# Power.net
KiCad netlist of a schematic drawn in Altium Designer
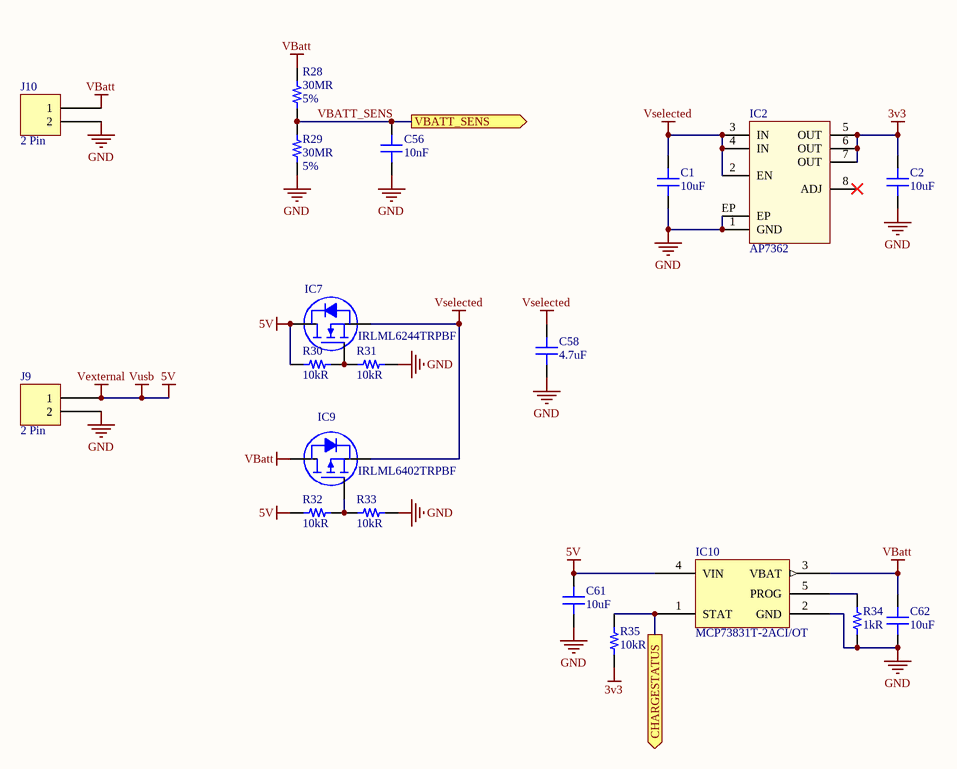
[diagram p0: Power.SchDoc]

(export (version "E")
  (design (tool "Eeschema 10.0.6"))
  (components
    (comp (ref "C1")
      (value "10uF")
      (footprint "CAP 0603/1608")
      (description "Ceramic, SMT Capacitor")
      (fields
        (field (name "MANUFACTURER") "Samsung")
        (field (name "MANUFACTURER PART NUMBER") "CL10A106MQ8NNNC")
      )
      (libsource (lib "yildizIoT Library") (part "Capacitor - Ceramic"))
    )
    (comp (ref "C2")
      (value "10uF")
      (footprint "CAP 0603/1608")
      (description "Ceramic, SMT Capacitor")
      (fields
        (field (name "MANUFACTURER") "Samsung")
        (field (name "MANUFACTURER PART NUMBER") "CL10A106MQ8NNNC")
      )
      (libsource (lib "yildizIoT Library") (part "Capacitor - Ceramic"))
    )
    (comp (ref "C56")
      (value "10nF")
      (footprint "CAP 0603/1608")
      (description "Ceramic, SMT Capacitor")
      (fields
        (field (name "MANUFACTURER") "KEMET")
        (field (name "MANUFACTURER PART NUMBER") "C0603C103J5RACTU")
      )
      (libsource (lib "yildizIoT Library") (part "Capacitor - Ceramic"))
    )
    (comp (ref "C58")
      (value "4.7uF")
      (footprint "CAP 0603/1608")
      (description "Ceramic, SMT Capacitor")
      (fields
        (field (name "MANUFACTURER") "Samsung")
        (field (name "MANUFACTURER PART NUMBER") "CL10A475MQ8NNNC")
      )
      (libsource (lib "yildizIoT Library") (part "Capacitor - Ceramic"))
    )
    (comp (ref "C61")
      (value "10uF")
      (footprint "CAP 0603/1608")
      (description "Ceramic, SMT Capacitor")
      (fields
        (field (name "MANUFACTURER") "Samsung")
        (field (name "MANUFACTURER PART NUMBER") "CL10A106MQ8NNNC")
      )
      (libsource (lib "yildizIoT Library") (part "Capacitor - Ceramic"))
    )
    (comp (ref "C62")
      (value "10uF")
      (footprint "CAP 0603/1608")
      (description "Ceramic, SMT Capacitor")
      (fields
        (field (name "MANUFACTURER") "Samsung")
        (field (name "MANUFACTURER PART NUMBER") "CL10A106MQ8NNNC")
      )
      (libsource (lib "yildizIoT Library") (part "Capacitor - Ceramic"))
    )
    (comp (ref "IC2")
      (value "AP7362")
      (footprint "DIODES SO-8-EP")
      (description "The AP7362 is a 1.5A adjustable output voltage linear regulator with ultra-low dropout.")
      (fields
        (field (name "MANUFACTURER") "Diodes")
        (field (name "MANUFACTURER PART NUMBER") "AP7362-33SP-13")
      )
      (libsource (lib "yildizIoT Library") (part "DIODES AP7362"))
    )
    (comp (ref "IC7")
      (value "IRLML6244TRPBF")
      (footprint "INFINEON SOT-23-3")
      (description "MOSFET N-CH 20V 6.3A SOT-23")
      (fields (field (name "MANUFACTURER") "International Rectifier"))
      (libsource (lib "Celestial Altium Library - altium_library") (part "INFINEON MOSFET N-CH SOT-23-3 GSD"))
    )
    (comp (ref "IC9")
      (value "IRLML6402TRPBF")
      (footprint "INFINEON SOT-23-3")
      (description "MOSFET P-CH 20V 3.7A SOT-23")
      (fields (field (name "MANUFACTURER") "International Rectifier"))
      (libsource (lib "Celestial Altium Library - altium_library") (part "INFINEON MOSFET P-CH SOT-23-3"))
    )
    (comp (ref "IC10")
      (value "MCP73831T-2ACI/OT")
      (footprint "MICROCHIP SOT-23-5 OT")
      (description "Miniature Single-Cell, Fully integrated Li-Ion, Li-Polymer charge management controllers")
      (fields (field (name "MANUFACTURER") "Microchip"))
      (libsource (lib "yildizIoT Library") (part "MICROCHIP MCP73831"))
    )
    (comp (ref "J9")
      (value "2 Pin")
      (footprint "JST XH B2B-XH-A")
      (libsource (lib "yildizIoT Library") (part "2 Pin"))
    )
    (comp (ref "J10")
      (value "2 Pin")
      (footprint "JST XH B2B-XH-A")
      (libsource (lib "yildizIoT Library") (part "2 Pin"))
    )
    (comp (ref "R28")
      (value "30MR")
      (footprint "RES 0603/1608")
      (description "Ceramic, SMT Capacitor")
      (fields
        (field (name "MANUFACTURER") "Vishay Dale")
        (field (name "MANUFACTURER PART NUMBER") "CRCW060330M0JPEAHR")
        (field (name "TOLERANCE") "5%")
      )
      (libsource (lib "yildizIoT Library") (part "Resistor_Chip"))
    )
    (comp (ref "R29")
      (value "30MR")
      (footprint "RES 0603/1608")
      (description "Ceramic, SMT Capacitor")
      (fields
        (field (name "MANUFACTURER") "Vishay Dale")
        (field (name "MANUFACTURER PART NUMBER") "CRCW060330M0JPEAHR")
        (field (name "TOLERANCE") "5%")
      )
      (libsource (lib "yildizIoT Library") (part "Resistor_Chip"))
    )
    (comp (ref "R30")
      (value "10kR")
      (footprint "RES 0603/1608")
      (description "Ceramic, SMT Capacitor")
      (fields
        (field (name "MANUFACTURER") "Stackpole Electronics")
        (field (name "MANUFACTURER PART NUMBER") "RNCP0603FTD10K0")
      )
      (libsource (lib "yildizIoT Library") (part "Resistor_Chip"))
    )
    (comp (ref "R31")
      (value "10kR")
      (footprint "RES 0603/1608")
      (description "Ceramic, SMT Capacitor")
      (fields
        (field (name "MANUFACTURER") "Stackpole Electronics")
        (field (name "MANUFACTURER PART NUMBER") "RNCP0603FTD10K0")
      )
      (libsource (lib "yildizIoT Library") (part "Resistor_Chip"))
    )
    (comp (ref "R32")
      (value "10kR")
      (footprint "RES 0603/1608")
      (description "Ceramic, SMT Capacitor")
      (fields
        (field (name "MANUFACTURER") "Stackpole Electronics")
        (field (name "MANUFACTURER PART NUMBER") "RNCP0603FTD10K0")
      )
      (libsource (lib "yildizIoT Library") (part "Resistor_Chip"))
    )
    (comp (ref "R33")
      (value "10kR")
      (footprint "RES 0603/1608")
      (description "Ceramic, SMT Capacitor")
      (fields
        (field (name "MANUFACTURER") "Stackpole Electronics")
        (field (name "MANUFACTURER PART NUMBER") "RNCP0603FTD10K0")
      )
      (libsource (lib "yildizIoT Library") (part "Resistor_Chip"))
    )
    (comp (ref "R34")
      (value "1kR")
      (footprint "RES 0603/1608")
      (description "Ceramic, SMT Capacitor")
      (fields (field (name "MANUFACTURER") "Rohm") (field (name "MANUFACTURER PART NUMBER") "ESR03EZPJ102"))
      (libsource (lib "yildizIoT Library") (part "Resistor_Chip"))
    )
    (comp (ref "R35")
      (value "10kR")
      (footprint "RES 0603/1608")
      (description "Ceramic, SMT Capacitor")
      (fields
        (field (name "MANUFACTURER") "Stackpole Electronics")
        (field (name "MANUFACTURER PART NUMBER") "RNCP0603FTD10K0")
      )
      (libsource (lib "yildizIoT Library") (part "Resistor_Chip"))
    )
  )
  (nets
    (net (code "1") (name "/CHARGESTATUS") (class "Default")
      (node (ref "IC10") (pin "1") (pinfunction "STAT_1") (pintype "passive"))
      (node (ref "R35") (pin "2") (pinfunction "2_2") (pintype "passive"))
    )
    (net (code "2") (name "/VBATT_SENS") (class "Default")
      (node (ref "C56") (pin "2") (pinfunction "2_2") (pintype "passive"))
      (node (ref "R28") (pin "1") (pinfunction "1_1") (pintype "passive"))
      (node (ref "R29") (pin "2") (pinfunction "2_2") (pintype "passive"))
    )
    (net (code "3") (name "3v3") (class "Default")
      (node (ref "C2") (pin "2") (pinfunction "2_2") (pintype "passive"))
      (node (ref "IC2") (pin "5") (pinfunction "OUT_5") (pintype "passive"))
      (node (ref "IC2") (pin "6") (pinfunction "OUT_6") (pintype "passive"))
      (node (ref "IC2") (pin "7") (pinfunction "OUT_7") (pintype "passive"))
      (node (ref "R35") (pin "1") (pinfunction "1_1") (pintype "passive"))
    )
    (net (code "4") (name "5V") (class "Default")
      (node (ref "C61") (pin "2") (pinfunction "2_2") (pintype "passive"))
      (node (ref "IC10") (pin "4") (pinfunction "VIN_4") (pintype "passive"))
      (node (ref "IC7") (pin "3") (pinfunction "D_3") (pintype "passive"))
      (node (ref "J9") (pin "1") (pinfunction "1_1") (pintype "passive"))
      (node (ref "R30") (pin "2") (pinfunction "2_2") (pintype "passive"))
      (node (ref "R32") (pin "2") (pinfunction "2_2") (pintype "passive"))
    )
    (net (code "5") (name "GND") (class "Default")
      (node (ref "C1") (pin "1") (pinfunction "1_1") (pintype "passive"))
      (node (ref "C2") (pin "1") (pinfunction "1_1") (pintype "passive"))
      (node (ref "C56") (pin "1") (pinfunction "1_1") (pintype "passive"))
      (node (ref "C58") (pin "1") (pinfunction "1_1") (pintype "passive"))
      (node (ref "C61") (pin "1") (pinfunction "1_1") (pintype "passive"))
      (node (ref "C62") (pin "1") (pinfunction "1_1") (pintype "passive"))
      (node (ref "IC10") (pin "2") (pinfunction "GND_2") (pintype "passive"))
      (node (ref "IC2") (pin "1") (pinfunction "GND_1") (pintype "passive"))
      (node (ref "IC2") (pin "EP") (pinfunction "EP_EP") (pintype "passive"))
      (node (ref "J10") (pin "2") (pinfunction "2_2") (pintype "passive"))
      (node (ref "J9") (pin "2") (pinfunction "2_2") (pintype "passive"))
      (node (ref "R29") (pin "1") (pinfunction "1_1") (pintype "passive"))
      (node (ref "R31") (pin "1") (pinfunction "1_1") (pintype "passive"))
      (node (ref "R33") (pin "1") (pinfunction "1_1") (pintype "passive"))
      (node (ref "R34") (pin "1") (pinfunction "1_1") (pintype "passive"))
    )
    (net (code "6") (name "Net-(IC7-G)") (class "Default")
      (node (ref "IC7") (pin "1") (pinfunction "G_1") (pintype "passive"))
      (node (ref "R30") (pin "1") (pinfunction "1_1") (pintype "passive"))
      (node (ref "R31") (pin "2") (pinfunction "2_2") (pintype "passive"))
    )
    (net (code "7") (name "Net-(IC9-G)") (class "Default")
      (node (ref "IC9") (pin "1") (pinfunction "G_1") (pintype "passive"))
      (node (ref "R32") (pin "1") (pinfunction "1_1") (pintype "passive"))
      (node (ref "R33") (pin "2") (pinfunction "2_2") (pintype "passive"))
    )
    (net (code "8") (name "Net-(IC10-PROG)") (class "Default")
      (node (ref "IC10") (pin "5") (pinfunction "PROG_5") (pintype "passive"))
      (node (ref "R34") (pin "2") (pinfunction "2_2") (pintype "passive"))
    )
    (net (code "9") (name "VBatt") (class "Default")
      (node (ref "C62") (pin "2") (pinfunction "2_2") (pintype "passive"))
      (node (ref "IC10") (pin "3") (pinfunction "VBAT_3") (pintype "output"))
      (node (ref "IC9") (pin "3") (pinfunction "D_3") (pintype "passive"))
      (node (ref "J10") (pin "1") (pinfunction "1_1") (pintype "passive"))
      (node (ref "R28") (pin "2") (pinfunction "2_2") (pintype "passive"))
    )
    (net (code "10") (name "Vselected") (class "Default")
      (node (ref "C1") (pin "2") (pinfunction "2_2") (pintype "passive"))
      (node (ref "C58") (pin "2") (pinfunction "2_2") (pintype "passive"))
      (node (ref "IC2") (pin "2") (pinfunction "EN_2") (pintype "passive"))
      (node (ref "IC2") (pin "3") (pinfunction "IN_3") (pintype "passive"))
      (node (ref "IC2") (pin "4") (pinfunction "IN_4") (pintype "passive"))
      (node (ref "IC7") (pin "2") (pinfunction "S_2") (pintype "passive"))
      (node (ref "IC9") (pin "2") (pinfunction "S_2") (pintype "passive"))
    )
    (net (code "11") (name "unconnected-(IC2-ADJ-Pad8)") (class "Default")
      (node (ref "IC2") (pin "8") (pinfunction "ADJ_8") (pintype "passive+no_connect"))
    )
  )
)
